# Final_PCB.net
KiCad netlist of a schematic drawn in Altium Designer
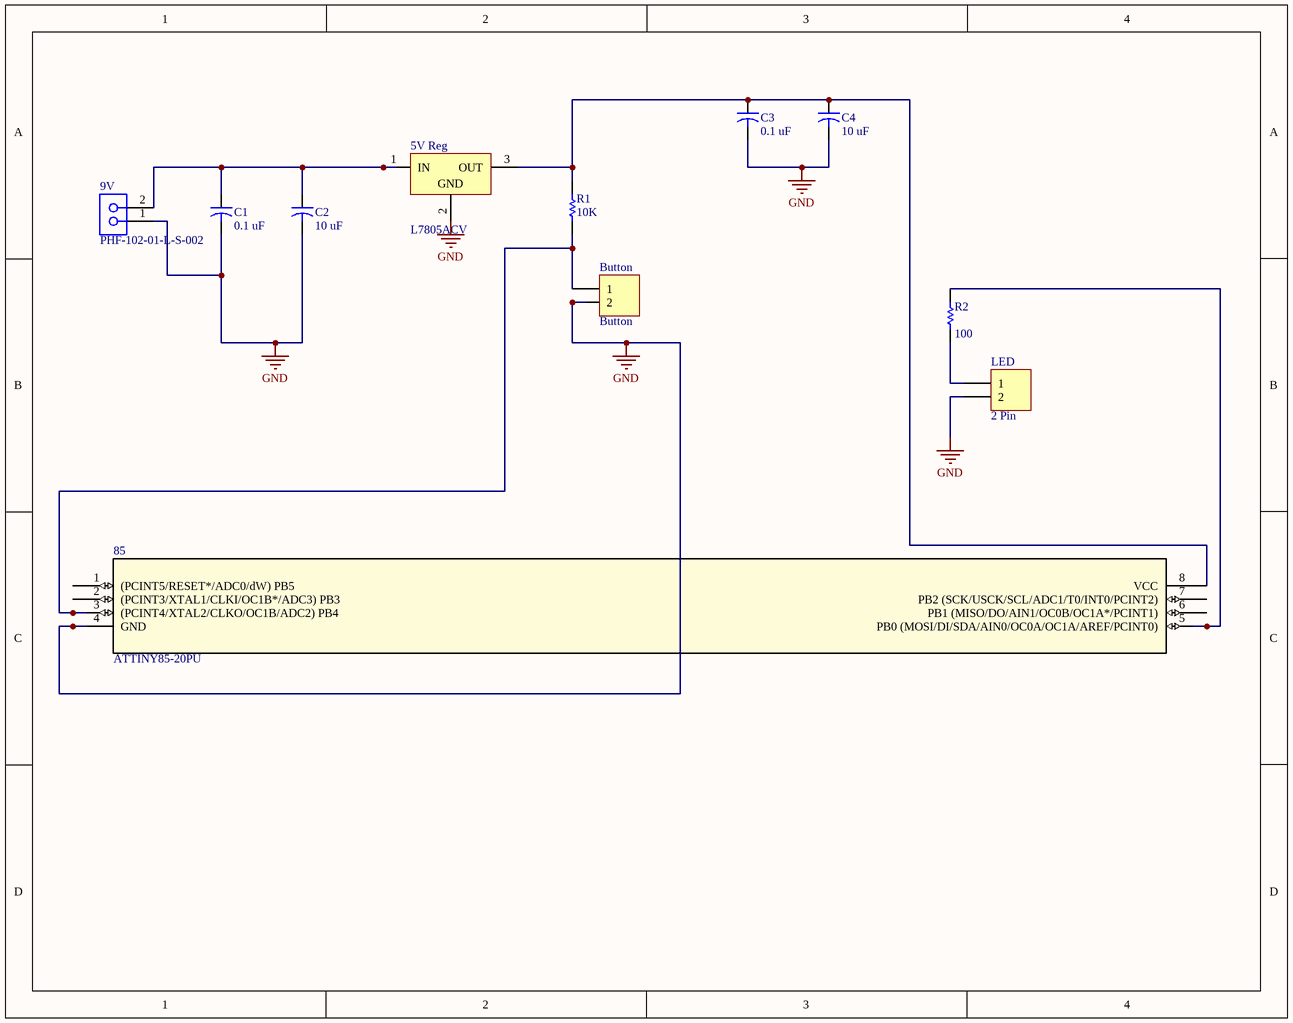
[diagram p0: Final PCB.SchDoc]

(export (version "E")
  (design (tool "Eeschema 10.0.6"))
  (components
    (comp (ref "5V Reg")
      (value "L7805ACV")
      (footprint "TO220")
      (description "Positive Voltage Regulator, 5V, 3-Pin TO-220")
      (libsource (lib "Integrated_Library - 11.11.18 - 23.08") (part "CMP-0244-00484-1"))
    )
    (comp (ref "9V")
      (value "PHF-102-01-L-S-002")
      (footprint "SMTC-PHF-102-01-X-S-002")
      (description "Press Fit Socket, Through-hole, Vertical, -55 to 125 degC, 2.54 mm Pitch, 2-Pin, Female, RoHS")
      (fields (field (name "MANUFACTURER") "Samtec"))
      (libsource (lib "Integrated_Library - 11.11.18 - 23.35") (part "CMP-1023-00103-1"))
    )
    (comp (ref "85")
      (value "ATTINY85-20PU")
      (footprint "8P3")
      (description "Imported")
      (libsource (lib "AltiumDesigner") (part "ATTINY85-20PU"))
    )
    (comp (ref "Button")
      (value "Button")
      (footprint "HDR1X2")
      (description "Header, 2-Pin")
      (fields (field (name "PUBLISHER") "Altium Limited"))
      (libsource (lib "Miscellaneous Connectors") (part "Header 2"))
    )
    (comp (ref "C1")
      (value "0.1 uF")
      (footprint "CAPR5-4X5")
      (description "Capacitor")
      (fields (field (name "Comment") "Cap2") (field (name "PUBLISHER") "Altium Limited"))
      (libsource (lib "Miscellaneous Devices") (part "Cap2"))
    )
    (comp (ref "C2")
      (value "10 uF")
      (footprint "CAPR5-4X5")
      (description "Capacitor")
      (fields (field (name "Comment") "Cap2") (field (name "PUBLISHER") "Altium Limited"))
      (libsource (lib "Miscellaneous Devices") (part "Cap2"))
    )
    (comp (ref "C3")
      (value "0.1 uF")
      (footprint "CAPR5-4X5")
      (description "Capacitor")
      (fields (field (name "Comment") "Cap2") (field (name "PUBLISHER") "Altium Limited"))
      (libsource (lib "Miscellaneous Devices") (part "Cap2"))
    )
    (comp (ref "C4")
      (value "10 uF")
      (footprint "CAPR5-4X5")
      (description "Capacitor")
      (fields (field (name "Comment") "Cap2") (field (name "PUBLISHER") "Altium Limited"))
      (libsource (lib "Miscellaneous Devices") (part "Cap2"))
    )
    (comp (ref "LED")
      (value "2 Pin")
      (footprint "HDR1X2")
      (description "Header, 2-Pin")
      (fields (field (name "PUBLISHER") "Altium Limited"))
      (libsource (lib "Miscellaneous Connectors") (part "Header 2"))
    )
    (comp (ref "R1")
      (value "10K")
      (footprint "AXIAL-0.3")
      (description "Resistor")
      (fields (field (name "PUBLISHER") "Altium Limited"))
      (libsource (lib "Miscellaneous Devices") (part "Res1"))
    )
    (comp (ref "R2")
      (value "100")
      (footprint "AXIAL-0.3")
      (description "Resistor")
      (fields (field (name "PUBLISHER") "Altium Limited"))
      (libsource (lib "Miscellaneous Devices") (part "Res1"))
    )
  )
  (nets
    (net (code "1") (name "GND") (class "Default")
      (node (ref "5V Reg") (pin "2") (pinfunction "GND_2") (pintype "power_in"))
      (node (ref "85") (pin "4") (pinfunction "GND_4") (pintype "power_in"))
      (node (ref "9V") (pin "1") (pinfunction "1_1") (pintype "passive"))
      (node (ref "Button") (pin "2") (pinfunction "2_2") (pintype "passive"))
      (node (ref "C1") (pin "2") (pinfunction "2_2") (pintype "passive"))
      (node (ref "C2") (pin "2") (pinfunction "2_2") (pintype "passive"))
      (node (ref "C3") (pin "2") (pinfunction "2_2") (pintype "passive"))
      (node (ref "C4") (pin "2") (pinfunction "2_2") (pintype "passive"))
      (node (ref "LED") (pin "2") (pinfunction "2_2") (pintype "passive"))
    )
    (net (code "2") (name "Net-(5V Reg-IN)") (class "Default")
      (node (ref "5V Reg") (pin "1") (pinfunction "IN_1") (pintype "power_in"))
      (node (ref "9V") (pin "2") (pinfunction "2_2") (pintype "passive"))
      (node (ref "C1") (pin "1") (pinfunction "1_1") (pintype "passive"))
      (node (ref "C2") (pin "1") (pinfunction "1_1") (pintype "passive"))
    )
    (net (code "3") (name "Net-(5V Reg-OUT)") (class "Default")
      (node (ref "5V Reg") (pin "3") (pinfunction "OUT_3") (pintype "power_in"))
      (node (ref "85") (pin "8") (pinfunction "VCC_8") (pintype "power_in"))
      (node (ref "C3") (pin "1") (pinfunction "1_1") (pintype "passive"))
      (node (ref "C4") (pin "1") (pinfunction "1_1") (pintype "passive"))
      (node (ref "R1") (pin "2") (pinfunction "2_2") (pintype "passive"))
    )
    (net (code "4") (name "Net-(85-(PCINT4{slash}XTAL2{slash}CLKO{slash}OC1B{slash}ADC2)_PB4)") (class "Default")
      (node (ref "85") (pin "3") (pinfunction "(PCINT4/XTAL2/CLKO/OC1B/ADC2)_PB4_3") (pintype "bidirectional"))
      (node (ref "Button") (pin "1") (pinfunction "1_1") (pintype "passive"))
      (node (ref "R1") (pin "1") (pinfunction "1_1") (pintype "passive"))
    )
    (net (code "5") (name "Net-(85-PB0_(MOSI{slash}DI{slash}SDA{slash}AIN0{slash}OC0A{slash}OC1A{slash}AREF{slash}PCINT0))") (class "Default")
      (node (ref "85") (pin "5") (pinfunction "PB0_(MOSI/DI/SDA/AIN0/OC0A/OC1A/AREF/PCINT0)_5") (pintype "bidirectional"))
      (node (ref "R2") (pin "2") (pinfunction "2_2") (pintype "passive"))
    )
    (net (code "6") (name "Net-(LED-Pad1)") (class "Default")
      (node (ref "LED") (pin "1") (pinfunction "1_1") (pintype "passive"))
      (node (ref "R2") (pin "1") (pinfunction "1_1") (pintype "passive"))
    )
    (net (code "7") (name "unconnected-(85-(PCINT3{slash}XTAL1{slash}CLKI{slash}OC1B*{slash}ADC3)_PB3-Pad2)") (class "Default")
      (node (ref "85") (pin "2") (pinfunction "(PCINT3/XTAL1/CLKI/OC1B*/ADC3)_PB3_2") (pintype "bidirectional"))
    )
    (net (code "8") (name "unconnected-(85-(PCINT5{slash}RESET*{slash}ADC0{slash}dW)_PB5-Pad1)") (class "Default")
      (node (ref "85") (pin "1") (pinfunction "(PCINT5/RESET*/ADC0/dW)_PB5_1") (pintype "bidirectional"))
    )
    (net (code "9") (name "unconnected-(85-PB1_(MISO{slash}DO{slash}AIN1{slash}OC0B{slash}OC1A*{slash}PCINT1)-Pad6)") (class "Default")
      (node (ref "85") (pin "6") (pinfunction "PB1_(MISO/DO/AIN1/OC0B/OC1A*/PCINT1)_6") (pintype "bidirectional"))
    )
    (net (code "10") (name "unconnected-(85-PB2_(SCK{slash}USCK{slash}SCL{slash}ADC1{slash}T0{slash}INT0{slash}PCINT2)-Pad7)") (class "Default")
      (node (ref "85") (pin "7") (pinfunction "PB2_(SCK/USCK/SCL/ADC1/T0/INT0/PCINT2)_7") (pintype "bidirectional"))
    )
  )
)
